# Sheet1.net
KiCad netlist of a schematic drawn in Altium Designer
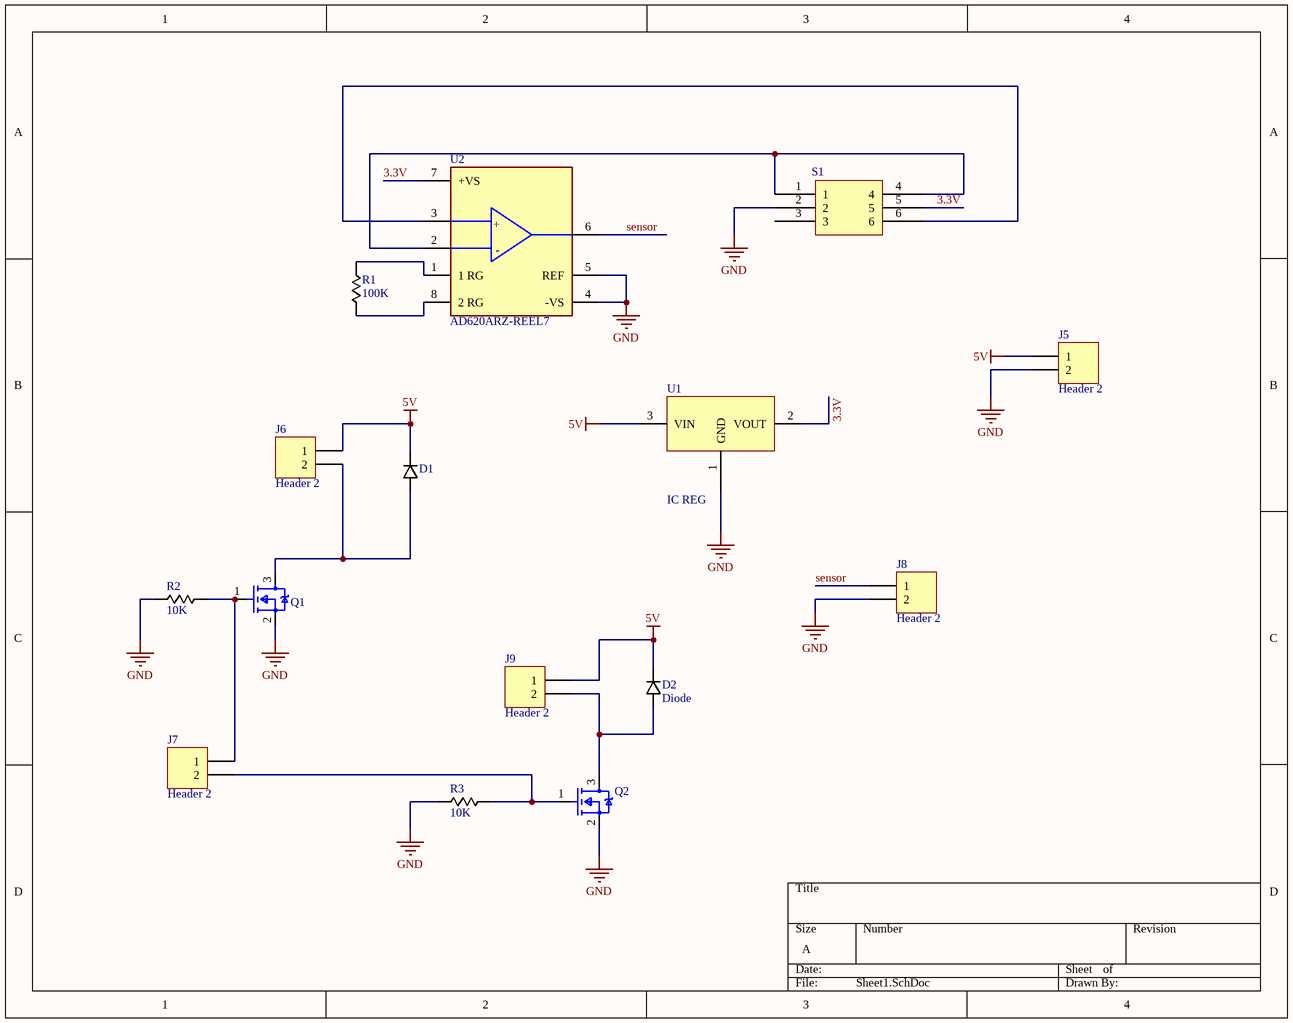
[diagram p0: Sheet1.SchDoc]

(export (version "E")
  (design (tool "Eeschema 10.0.6"))
  (components
    (comp (ref "D1") (value "Diode") (footprint "DIODE SMA") (libsource (lib "HassanLib") (part "Diode")))
    (comp (ref "D2") (value "Diode") (footprint "DIODE SMA") (libsource (lib "HassanLib") (part "Diode")))
    (comp (ref "J5")
      (value "Header 2")
      (footprint "HDR1X2")
      (description "Header, 2-Pin")
      (fields (field (name "PUBLISHER") "Altium Limited"))
      (libsource (lib "") (part "Header 2_1"))
    )
    (comp (ref "J6")
      (value "Header 2")
      (footprint "HDR1X2")
      (description "Header, 2-Pin")
      (fields (field (name "PUBLISHER") "Altium Limited"))
      (libsource (lib "Miscellaneous Connectors") (part "Header 2"))
    )
    (comp (ref "J7")
      (value "Header 2")
      (footprint "HDR1X2")
      (description "Header, 2-Pin")
      (fields (field (name "PUBLISHER") "Altium Limited"))
      (libsource (lib "Miscellaneous Connectors") (part "Header 2"))
    )
    (comp (ref "J8")
      (value "Header 2")
      (footprint "HDR1X2")
      (description "Header, 2-Pin")
      (fields (field (name "PUBLISHER") "Altium Limited"))
      (libsource (lib "") (part "Header 2_1"))
    )
    (comp (ref "J9")
      (value "Header 2")
      (footprint "HDR1X2")
      (description "Header, 2-Pin")
      (fields (field (name "PUBLISHER") "Altium Limited"))
      (libsource (lib "Miscellaneous Connectors") (part "Header 2"))
    )
    (comp (ref "Q1")
      (value "IRLZ44NPbF")
      (footprint "SOT23")
      (description "MOSFET N-CH 55V 47A TO220AB")
      (libsource (lib "HassanLib") (part "MOSFET N"))
    )
    (comp (ref "Q2")
      (value "IRLZ44NPbF")
      (footprint "SOT23")
      (description "MOSFET N-CH 55V 47A TO220AB")
      (libsource (lib "HassanLib") (part "MOSFET N"))
    )
    (comp (ref "R1") (value "100K") (footprint "0402") (libsource (lib "HassanLib") (part "RESISTOR")))
    (comp (ref "R2") (value "10K") (footprint "0402") (libsource (lib "HassanLib") (part "RESISTOR")))
    (comp (ref "R3") (value "10K") (footprint "0402") (libsource (lib "HassanLib") (part "RESISTOR")))
    (comp (ref "S1")
      (value "IC 6 PINS")
      (footprint "Pressure_sensor")
      (libsource (lib "HassanLib") (part "IC 6 PINS"))
    )
    (comp (ref "U1") (value "IC REG") (footprint "SOT23") (libsource (lib "HassanLib") (part "IC REG")))
    (comp (ref "U2")
      (value "AD620ARZ-REEL7")
      (footprint "FP-R-8-IPC_B")
      (description "IC INST AMP 1 CIRCUIT 8SOIC")
      (libsource (lib "Altium Content Vault") (part "0450056d8b8a4b7768ba406df0ba6bf"))
    )
  )
  (nets
    (net (code "1") (name "/3.3V") (class "Default")
      (node (ref "S1") (pin "5") (pinfunction "5_5") (pintype "passive"))
      (node (ref "U1") (pin "2") (pinfunction "VOUT_2") (pintype "passive"))
      (node (ref "U2") (pin "7") (pinfunction "+VS_7") (pintype "power_in"))
    )
    (net (code "2") (name "/sensor") (class "Default")
      (node (ref "J8") (pin "1") (pinfunction "1_1") (pintype "passive"))
      (node (ref "U2") (pin "6") (pinfunction "OUTPUT_6") (pintype "passive"))
    )
    (net (code "3") (name "5V") (class "Default")
      (node (ref "D1") (pin "2") (pinfunction "K_2") (pintype "passive"))
      (node (ref "D2") (pin "2") (pinfunction "K_2") (pintype "passive"))
      (node (ref "J5") (pin "1") (pinfunction "1_1") (pintype "passive"))
      (node (ref "J6") (pin "1") (pinfunction "1_1") (pintype "passive"))
      (node (ref "J9") (pin "1") (pinfunction "1_1") (pintype "passive"))
      (node (ref "U1") (pin "3") (pinfunction "VIN_3") (pintype "passive"))
    )
    (net (code "4") (name "GND") (class "Default")
      (node (ref "J5") (pin "2") (pinfunction "2_2") (pintype "passive"))
      (node (ref "J8") (pin "2") (pinfunction "2_2") (pintype "passive"))
      (node (ref "Q1") (pin "2") (pinfunction "S_2") (pintype "passive"))
      (node (ref "Q2") (pin "2") (pinfunction "S_2") (pintype "passive"))
      (node (ref "R2") (pin "1") (pinfunction "1_1") (pintype "passive"))
      (node (ref "R3") (pin "1") (pinfunction "1_1") (pintype "passive"))
      (node (ref "S1") (pin "2") (pinfunction "2_2") (pintype "passive"))
      (node (ref "U1") (pin "1") (pinfunction "GND_1") (pintype "passive"))
      (node (ref "U2") (pin "4") (pinfunction "-VS_4") (pintype "power_in"))
      (node (ref "U2") (pin "5") (pinfunction "REF_5") (pintype "passive"))
    )
    (net (code "5") (name "Net-(D1-A)") (class "Default")
      (node (ref "D1") (pin "1") (pinfunction "A_1") (pintype "passive"))
      (node (ref "J6") (pin "2") (pinfunction "2_2") (pintype "passive"))
      (node (ref "Q1") (pin "3") (pinfunction "D_3") (pintype "passive"))
    )
    (net (code "6") (name "Net-(D2-A)") (class "Default")
      (node (ref "D2") (pin "1") (pinfunction "A_1") (pintype "passive"))
      (node (ref "J9") (pin "2") (pinfunction "2_2") (pintype "passive"))
      (node (ref "Q2") (pin "3") (pinfunction "D_3") (pintype "passive"))
    )
    (net (code "7") (name "Net-(Q1-G)") (class "Default")
      (node (ref "J7") (pin "1") (pinfunction "1_1") (pintype "passive"))
      (node (ref "Q1") (pin "1") (pinfunction "G_1") (pintype "passive"))
      (node (ref "R2") (pin "2") (pinfunction "2_2") (pintype "passive"))
    )
    (net (code "8") (name "Net-(Q2-G)") (class "Default")
      (node (ref "J7") (pin "2") (pinfunction "2_2") (pintype "passive"))
      (node (ref "Q2") (pin "1") (pinfunction "G_1") (pintype "passive"))
      (node (ref "R3") (pin "2") (pinfunction "2_2") (pintype "passive"))
    )
    (net (code "9") (name "Net-(U2-+IN)") (class "Default")
      (node (ref "S1") (pin "6") (pinfunction "6_6") (pintype "passive"))
      (node (ref "U2") (pin "3") (pinfunction "+IN_3") (pintype "tri_state"))
    )
    (net (code "10") (name "Net-(U2--IN)") (class "Default")
      (node (ref "S1") (pin "1") (pinfunction "1_1") (pintype "passive"))
      (node (ref "S1") (pin "4") (pinfunction "4_4") (pintype "passive"))
      (node (ref "U2") (pin "2") (pinfunction "-IN_2") (pintype "tri_state"))
    )
    (net (code "11") (name "Net-(U2-1_RG)") (class "Default")
      (node (ref "R1") (pin "2") (pinfunction "2_2") (pintype "passive"))
      (node (ref "U2") (pin "1") (pinfunction "1_RG_1") (pintype "passive"))
    )
    (net (code "12") (name "Net-(U2-2_RG)") (class "Default")
      (node (ref "R1") (pin "1") (pinfunction "1_1") (pintype "passive"))
      (node (ref "U2") (pin "8") (pinfunction "2_RG_8") (pintype "passive"))
    )
    (net (code "13") (name "unconnected-(S1-Pad3)") (class "Default")
      (node (ref "S1") (pin "3") (pinfunction "3_3") (pintype "passive"))
    )
  )
)
